# XMICRO-MEMORY_V1_0.net
KiCad netlist of a schematic drawn in EAGLE
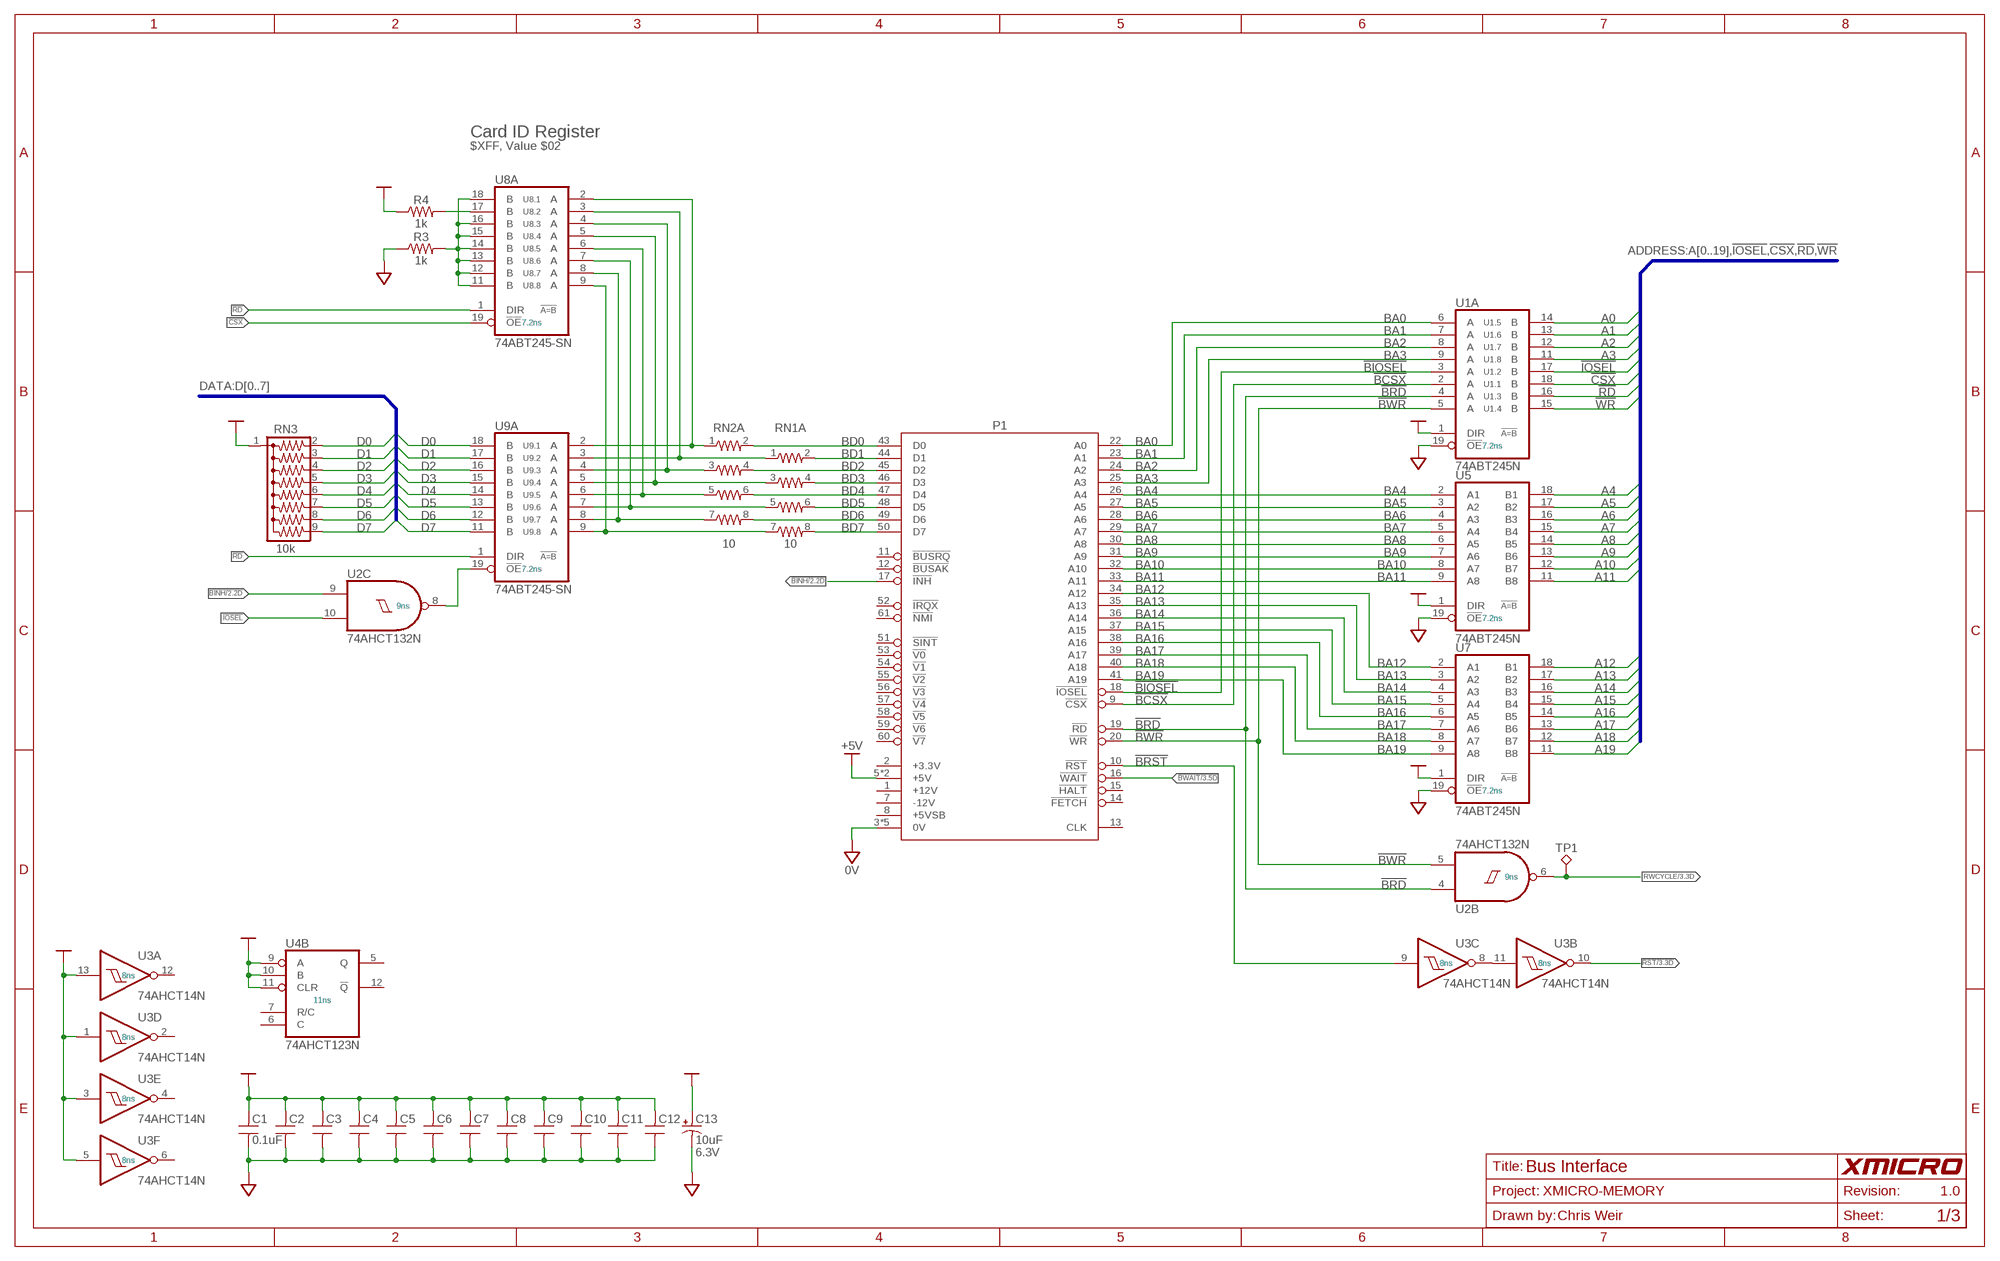
[diagram p0: schematic, sheet 1]
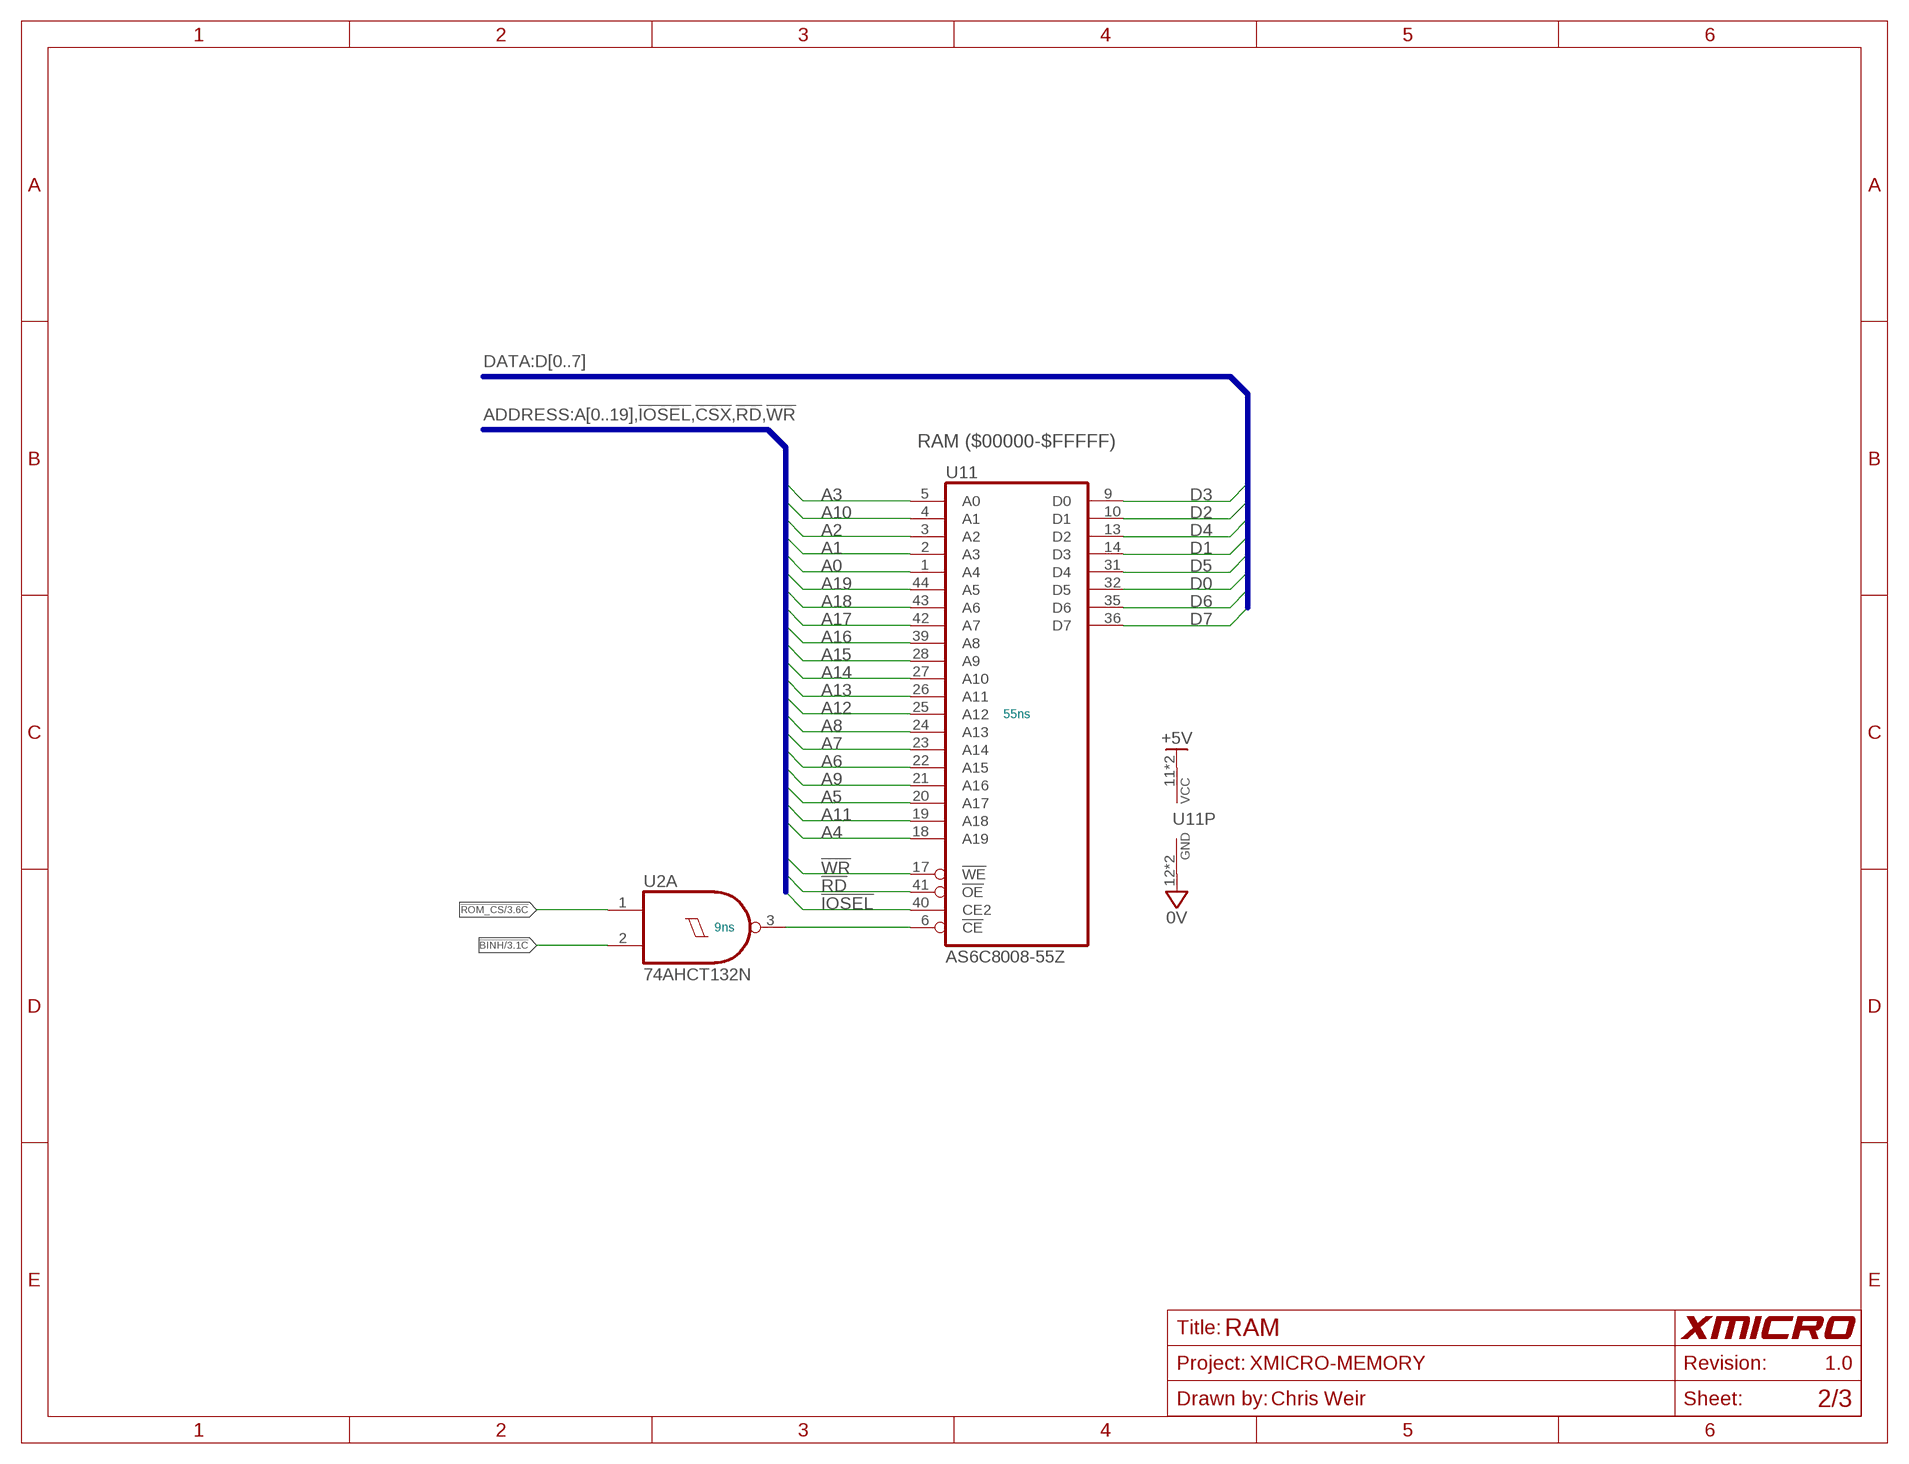
[diagram p1: schematic, sheet 2]
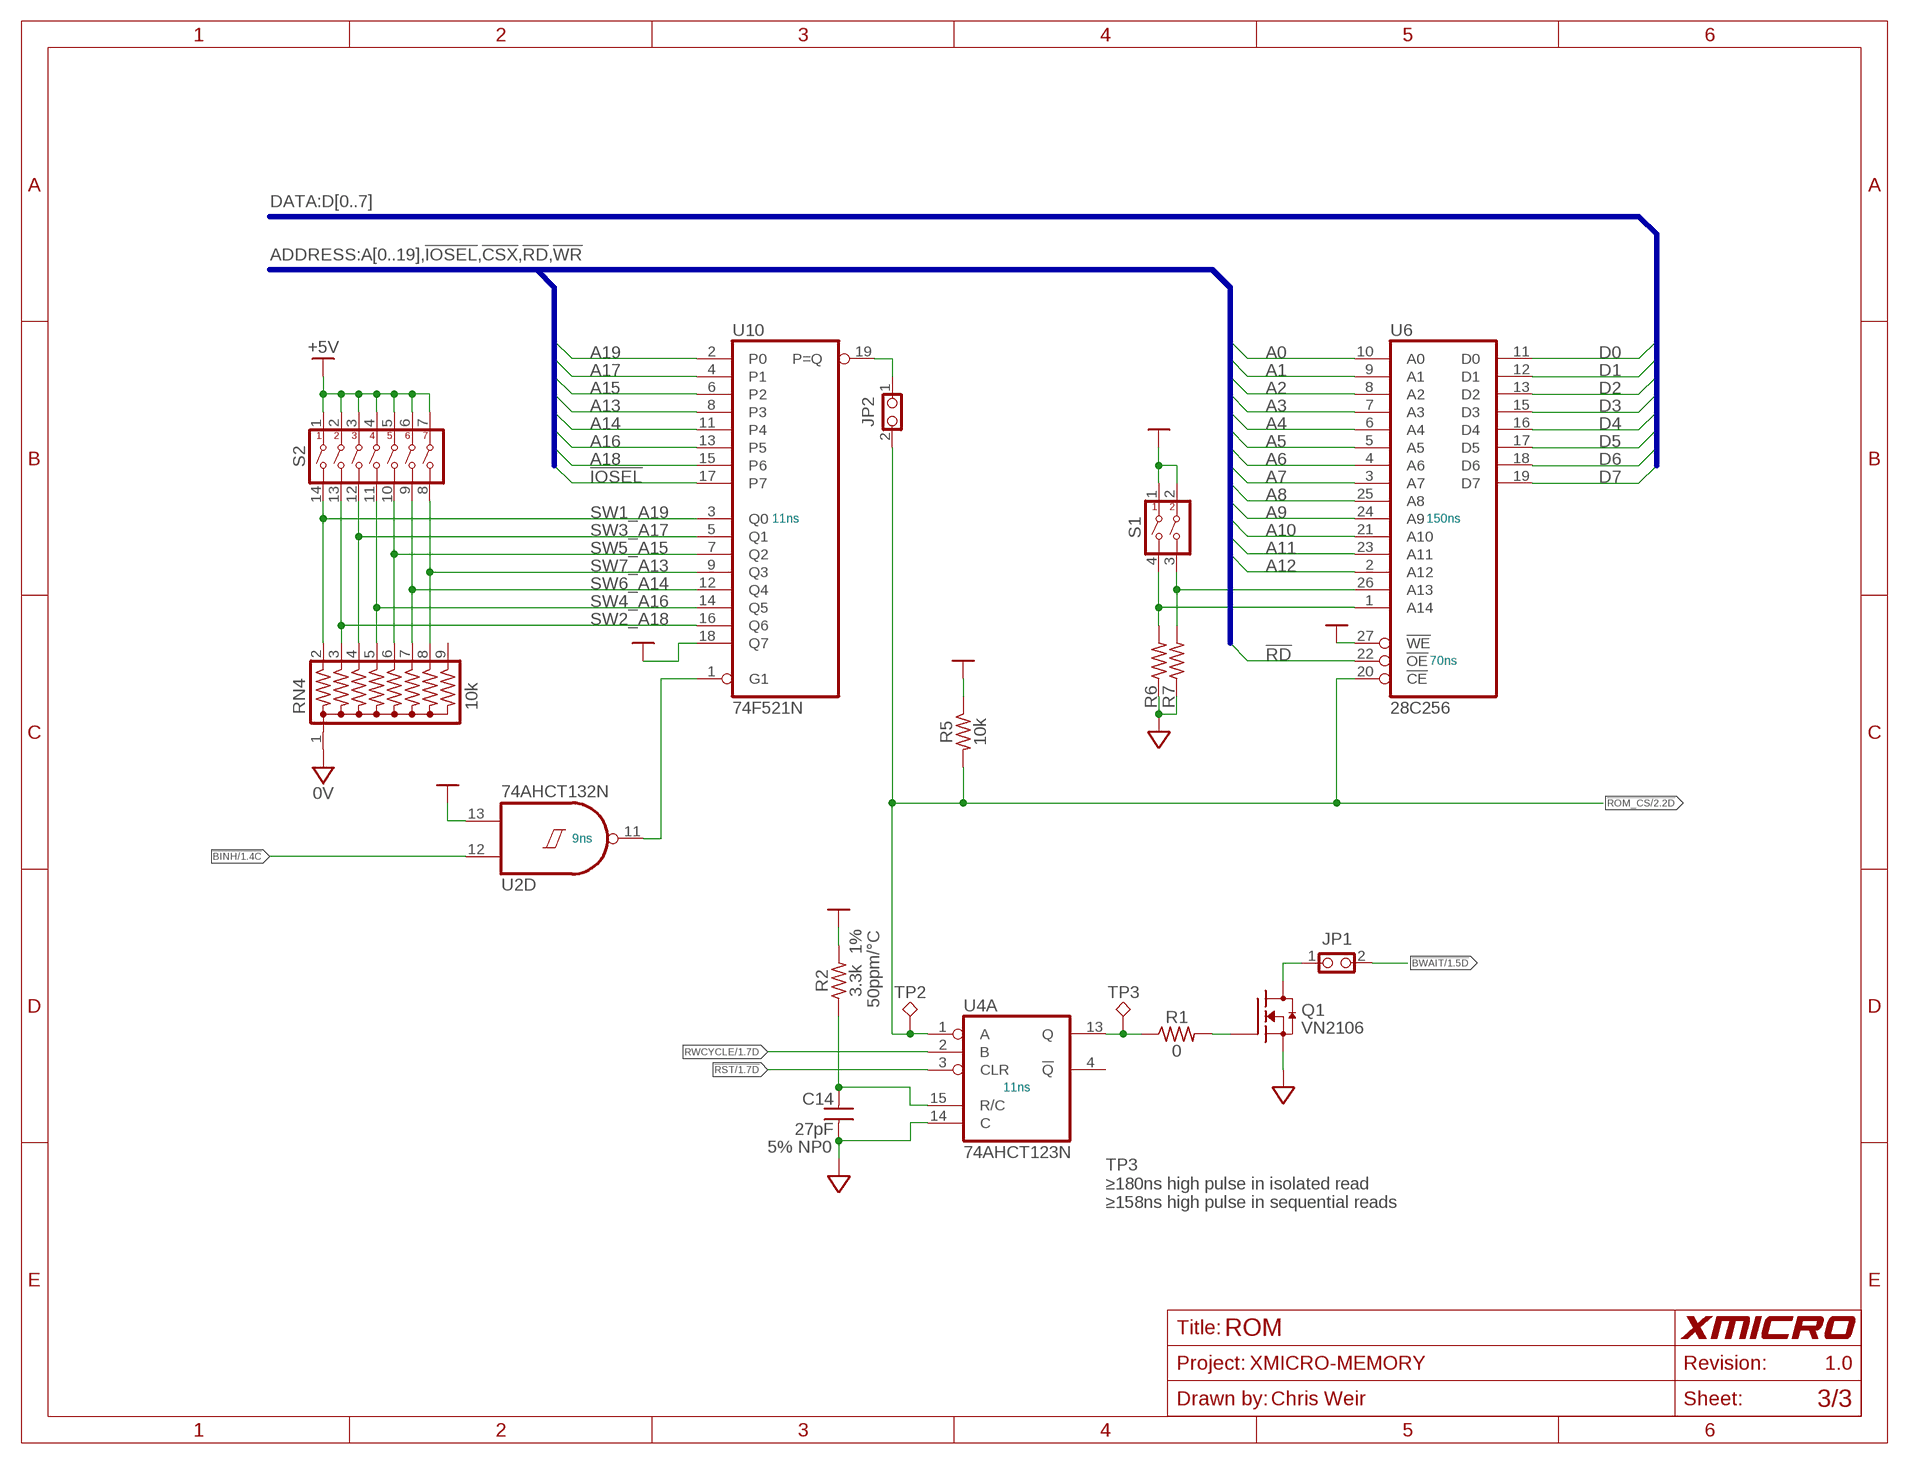
[diagram p2: schematic, sheet 3]

(export (version "E")
  (design (tool "Eeschema 10.0.6"))
  (components
    (comp (ref "C14")
      (value "27pF")
      (footprint "eagle-import:C025-024X044")
      (fields (field (name "TC") "NP0") (field (name "TOLERANCE") "5%"))
      (libsource (lib "eagle-import") (part "C-US025-024X044"))
    )
    (comp (ref "JP1")
      (value "1X2-THRU")
      (footprint "eagle-import:1X2")
      (libsource (lib "eagle-import") (part "1X2-THRU"))
    )
    (comp (ref "JP2")
      (value "1X2-THRU")
      (footprint "eagle-import:1X2")
      (libsource (lib "eagle-import") (part "1X2-THRU"))
    )
    (comp (ref "Q1")
      (value "VN2106")
      (footprint "eagle-import:TO92")
      (libsource (lib "eagle-import") (part "VN2106"))
    )
    (comp (ref "R1")
      (value "0")
      (footprint "eagle-import:0207_10")
      (libsource (lib "eagle-import") (part "R-US_0207/10"))
    )
    (comp (ref "R2")
      (value "3.3k")
      (footprint "eagle-import:0207_10")
      (fields (field (name "TC") "50ppm/°C") (field (name "TOLERANCE") "1%"))
      (libsource (lib "eagle-import") (part "R-US_0207/10"))
    )
    (comp (ref "R5")
      (value "10k")
      (footprint "eagle-import:0207_10")
      (libsource (lib "eagle-import") (part "R-US_0207/10"))
    )
    (comp (ref "R6")
      (value "10k")
      (footprint "eagle-import:0207_10")
      (libsource (lib "eagle-import") (part "R-US_0207/10"))
    )
    (comp (ref "R7")
      (value "10k")
      (footprint "eagle-import:0207_10")
      (libsource (lib "eagle-import") (part "R-US_0207/10"))
    )
    (comp (ref "RN4")
      (value "10k")
      (footprint "eagle-import:SIL9")
      (libsource (lib "eagle-import") (part "G08R"))
    )
    (comp (ref "S1")
      (value "SW-DIP02")
      (footprint "eagle-import:SW-DIP2")
      (libsource (lib "eagle-import") (part "SW-DIP02"))
    )
    (comp (ref "S2")
      (value "SW-DIP07")
      (footprint "eagle-import:SW-DIP7")
      (libsource (lib "eagle-import") (part "SW-DIP07"))
    )
    (comp (ref "TP2")
      (value "TP-040")
      (footprint "eagle-import:TP-040")
      (libsource (lib "eagle-import") (part "TP-040"))
    )
    (comp (ref "TP3")
      (value "TP-040")
      (footprint "eagle-import:TP-040")
      (libsource (lib "eagle-import") (part "TP-040"))
    )
    (comp (ref "U2")
      (value "74AHCT132N")
      (footprint "eagle-import:DIL14")
      (libsource (lib "eagle-import") (part "74132NAHCT"))
    )
    (comp (ref "U4")
      (value "74AHCT123N")
      (footprint "eagle-import:DIL16")
      (fields (field (name "TPD") "11ns"))
      (libsource (lib "eagle-import") (part "74123NAHCT"))
    )
    (comp (ref "U6")
      (value "28C256")
      (footprint "eagle-import:228-1277-00")
      (libsource (lib "eagle-import") (part "28256-P-ZC"))
    )
    (comp (ref "U10")
      (value "74F521N")
      (footprint "eagle-import:DIL20")
      (fields (field (name "TPD") "11ns"))
      (libsource (lib "eagle-import") (part "74521NF"))
    )
    (comp (ref "C1")
      (value "0.1uF")
      (footprint "eagle-import:C025-024X044")
      (libsource (lib "eagle-import") (part "C-US025-024X044"))
    )
    (comp (ref "C2")
      (value "0.1uF")
      (footprint "eagle-import:C025-024X044")
      (libsource (lib "eagle-import") (part "C-US025-024X044"))
    )
    (comp (ref "C3")
      (value "0.1uF")
      (footprint "eagle-import:C025-024X044")
      (libsource (lib "eagle-import") (part "C-US025-024X044"))
    )
    (comp (ref "C4")
      (value "0.1uF")
      (footprint "eagle-import:C025-024X044")
      (libsource (lib "eagle-import") (part "C-US025-024X044"))
    )
    (comp (ref "C5")
      (value "0.1uF")
      (footprint "eagle-import:C025-024X044")
      (libsource (lib "eagle-import") (part "C-US025-024X044"))
    )
    (comp (ref "C6")
      (value "0.1uF")
      (footprint "eagle-import:C025-024X044")
      (libsource (lib "eagle-import") (part "C-US025-024X044"))
    )
    (comp (ref "C7")
      (value "0.1uF")
      (footprint "eagle-import:C025-024X044")
      (libsource (lib "eagle-import") (part "C-US025-024X044"))
    )
    (comp (ref "C8")
      (value "0.1uF")
      (footprint "eagle-import:C025-024X044")
      (libsource (lib "eagle-import") (part "C-US025-024X044"))
    )
    (comp (ref "C9")
      (value "0.1uF")
      (footprint "eagle-import:C025-024X044")
      (libsource (lib "eagle-import") (part "C-US025-024X044"))
    )
    (comp (ref "C10")
      (value "0.1uF")
      (footprint "eagle-import:C025-024X044")
      (libsource (lib "eagle-import") (part "C-US025-024X044"))
    )
    (comp (ref "C11")
      (value "0.1uF")
      (footprint "eagle-import:C025-024X044")
      (libsource (lib "eagle-import") (part "C-US025-024X044"))
    )
    (comp (ref "C12")
      (value "0.1uF")
      (footprint "eagle-import:C025-024X044")
      (libsource (lib "eagle-import") (part "C-US025-024X044"))
    )
    (comp (ref "C13")
      (value "10uF")
      (footprint "eagle-import:E2,5-6")
      (fields (field (name "VOLTAGE") "6.3V"))
      (libsource (lib "eagle-import") (part "CPOL-USE2.5-6"))
    )
    (comp (ref "P1")
      (value "XMICRO-BUS-EDGE")
      (footprint "eagle-import:EDGE62M")
      (libsource (lib "eagle-import") (part "XMICRO-BUS-EDGE"))
    )
    (comp (ref "R3")
      (value "1k")
      (footprint "eagle-import:0207_10")
      (libsource (lib "eagle-import") (part "R-US_0207/10"))
    )
    (comp (ref "R4")
      (value "1k")
      (footprint "eagle-import:0207_10")
      (libsource (lib "eagle-import") (part "R-US_0207/10"))
    )
    (comp (ref "RN1")
      (value "10")
      (footprint "eagle-import:SIL8")
      (libsource (lib "eagle-import") (part "E4R"))
    )
    (comp (ref "RN2")
      (value "10")
      (footprint "eagle-import:SIL8")
      (libsource (lib "eagle-import") (part "E4R"))
    )
    (comp (ref "RN3")
      (value "10k")
      (footprint "eagle-import:SIL9")
      (libsource (lib "eagle-import") (part "G08R"))
    )
    (comp (ref "TP1")
      (value "TP-040")
      (footprint "eagle-import:TP-040")
      (libsource (lib "eagle-import") (part "TP-040"))
    )
    (comp (ref "U1")
      (value "74ABT245N")
      (footprint "eagle-import:DIL20")
      (libsource (lib "eagle-import") (part "74245-SNABT"))
    )
    (comp (ref "U3")
      (value "74AHCT14N")
      (footprint "eagle-import:DIL14")
      (fields (field (name "TPD") "8ns") (field (name "TPD_1") "8ns"))
      (libsource (lib "eagle-import") (part "7414NAHCT"))
    )
    (comp (ref "U5")
      (value "74ABT245N")
      (footprint "eagle-import:DIL20")
      (libsource (lib "eagle-import") (part "74245NABT"))
    )
    (comp (ref "U7")
      (value "74ABT245N")
      (footprint "eagle-import:DIL20")
      (libsource (lib "eagle-import") (part "74245NABT"))
    )
    (comp (ref "U8")
      (value "74ABT245-SN")
      (footprint "eagle-import:DIL20")
      (libsource (lib "eagle-import") (part "74245-SNABT"))
    )
    (comp (ref "U9")
      (value "74ABT245-SN")
      (footprint "eagle-import:DIL20")
      (libsource (lib "eagle-import") (part "74245-SNABT"))
    )
    (comp (ref "U11")
      (value "AS6C8008-55Z")
      (footprint "eagle-import:TSOP44-II")
      (libsource (lib "eagle-import") (part "AS6C8008-55Z"))
    )
  )
  (nets
    (net (code "28") (name "+5V") (class "Default")
      (node (ref "C1") (pin "1") (pinfunction "1_1") (pintype "passive"))
      (node (ref "C10") (pin "1") (pinfunction "1_1") (pintype "passive"))
      (node (ref "C11") (pin "1") (pinfunction "1_1") (pintype "passive"))
      (node (ref "C12") (pin "1") (pinfunction "1_1") (pintype "passive"))
      (node (ref "C13") (pin "+") (pinfunction "+_+") (pintype "passive"))
      (node (ref "C2") (pin "1") (pinfunction "1_1") (pintype "passive"))
      (node (ref "C3") (pin "1") (pinfunction "1_1") (pintype "passive"))
      (node (ref "C4") (pin "1") (pinfunction "1_1") (pintype "passive"))
      (node (ref "C5") (pin "1") (pinfunction "1_1") (pintype "passive"))
      (node (ref "C6") (pin "1") (pinfunction "1_1") (pintype "passive"))
      (node (ref "C7") (pin "1") (pinfunction "1_1") (pintype "passive"))
      (node (ref "C8") (pin "1") (pinfunction "1_1") (pintype "passive"))
      (node (ref "C9") (pin "1") (pinfunction "1_1") (pintype "passive"))
      (node (ref "P1") (pin "5") (pinfunction "+5V_5") (pintype "bidirectional"))
      (node (ref "P1") (pin "6") (pinfunction "+5V_6") (pintype "bidirectional"))
      (node (ref "R2") (pin "2") (pinfunction "2_2") (pintype "passive"))
      (node (ref "R4") (pin "1") (pinfunction "1_1") (pintype "passive"))
      (node (ref "R5") (pin "1") (pinfunction "1_1") (pintype "passive"))
      (node (ref "RN3") (pin "1") (pinfunction "1_1") (pintype "passive"))
      (node (ref "S1") (pin "1") (pinfunction "1_1") (pintype "passive"))
      (node (ref "S1") (pin "2") (pinfunction "2_2") (pintype "passive"))
      (node (ref "S2") (pin "1") (pinfunction "1_1") (pintype "passive"))
      (node (ref "S2") (pin "2") (pinfunction "2_2") (pintype "passive"))
      (node (ref "S2") (pin "3") (pinfunction "3_3") (pintype "passive"))
      (node (ref "S2") (pin "4") (pinfunction "4_4") (pintype "passive"))
      (node (ref "S2") (pin "5") (pinfunction "5_5") (pintype "passive"))
      (node (ref "S2") (pin "6") (pinfunction "6_6") (pintype "passive"))
      (node (ref "S2") (pin "7") (pinfunction "7_7") (pintype "passive"))
      (node (ref "U1") (pin "1") (pinfunction "DIR_1") (pintype "input"))
      (node (ref "U10") (pin "18") (pinfunction "Q7_18") (pintype "input"))
      (node (ref "U11") (pin "11") (pinfunction "+5V_11") (pintype "power_in"))
      (node (ref "U11") (pin "33") (pinfunction "+5V_33") (pintype "power_in"))
      (node (ref "U2") (pin "13") (pinfunction "I1_13") (pintype "input"))
      (node (ref "U3") (pin "1") (pinfunction "I_1") (pintype "input"))
      (node (ref "U3") (pin "13") (pinfunction "I_13") (pintype "input"))
      (node (ref "U3") (pin "3") (pinfunction "I_3") (pintype "input"))
      (node (ref "U3") (pin "5") (pinfunction "I_5") (pintype "input"))
      (node (ref "U4") (pin "10") (pinfunction "B_10") (pintype "input"))
      (node (ref "U4") (pin "11") (pinfunction "CLR_11") (pintype "input"))
      (node (ref "U4") (pin "9") (pinfunction "A_9") (pintype "input"))
      (node (ref "U5") (pin "1") (pinfunction "DIR_1") (pintype "input"))
      (node (ref "U6") (pin "27") (pinfunction "~{WE}_27") (pintype "input"))
      (node (ref "U7") (pin "1") (pinfunction "DIR_1") (pintype "input"))
    )
    (net (code "35") (name "0V") (class "Default")
      (node (ref "C1") (pin "2") (pinfunction "2_2") (pintype "passive"))
      (node (ref "C10") (pin "2") (pinfunction "2_2") (pintype "passive"))
      (node (ref "C11") (pin "2") (pinfunction "2_2") (pintype "passive"))
      (node (ref "C12") (pin "2") (pinfunction "2_2") (pintype "passive"))
      (node (ref "C13") (pin "-") (pinfunction "-_-") (pintype "passive"))
      (node (ref "C14") (pin "2") (pinfunction "2_2") (pintype "passive"))
      (node (ref "C2") (pin "2") (pinfunction "2_2") (pintype "passive"))
      (node (ref "C3") (pin "2") (pinfunction "2_2") (pintype "passive"))
      (node (ref "C4") (pin "2") (pinfunction "2_2") (pintype "passive"))
      (node (ref "C5") (pin "2") (pinfunction "2_2") (pintype "passive"))
      (node (ref "C6") (pin "2") (pinfunction "2_2") (pintype "passive"))
      (node (ref "C7") (pin "2") (pinfunction "2_2") (pintype "passive"))
      (node (ref "C8") (pin "2") (pinfunction "2_2") (pintype "passive"))
      (node (ref "C9") (pin "2") (pinfunction "2_2") (pintype "passive"))
      (node (ref "P1") (pin "21") (pinfunction "0V_21") (pintype "bidirectional"))
      (node (ref "P1") (pin "3") (pinfunction "0V_3") (pintype "bidirectional"))
      (node (ref "P1") (pin "4") (pinfunction "0V_4") (pintype "bidirectional"))
      (node (ref "P1") (pin "42") (pinfunction "0V_42") (pintype "bidirectional"))
      (node (ref "P1") (pin "62") (pinfunction "0V_62") (pintype "bidirectional"))
      (node (ref "Q1") (pin "1") (pinfunction "S_1") (pintype "passive"))
      (node (ref "R3") (pin "1") (pinfunction "1_1") (pintype "passive"))
      (node (ref "R6") (pin "1") (pinfunction "1_1") (pintype "passive"))
      (node (ref "R7") (pin "1") (pinfunction "1_1") (pintype "passive"))
      (node (ref "RN4") (pin "1") (pinfunction "1_1") (pintype "passive"))
      (node (ref "U1") (pin "19") (pinfunction "~{OE}_19") (pintype "input"))
      (node (ref "U11") (pin "12") (pinfunction "0V_12") (pintype "power_in"))
      (node (ref "U11") (pin "34") (pinfunction "0V_34") (pintype "power_in"))
      (node (ref "U4") (pin "14") (pinfunction "C_14") (pintype "input"))
      (node (ref "U5") (pin "19") (pinfunction "~{OE}_19") (pintype "input"))
      (node (ref "U7") (pin "19") (pinfunction "~{OE}_19") (pintype "input"))
    )
    (net (code "36") (name "A0") (class "Default")
      (node (ref "U1") (pin "14") (pinfunction "B_14") (pintype "bidirectional"))
      (node (ref "U11") (pin "1") (pinfunction "A4_1") (pintype "input"))
      (node (ref "U6") (pin "10") (pinfunction "A0_10") (pintype "input"))
    )
    (net (code "37") (name "A1") (class "Default")
      (node (ref "U1") (pin "13") (pinfunction "B_13") (pintype "bidirectional"))
      (node (ref "U11") (pin "2") (pinfunction "A3_2") (pintype "input"))
      (node (ref "U6") (pin "9") (pinfunction "A1_9") (pintype "input"))
    )
    (net (code "38") (name "A2") (class "Default")
      (node (ref "U1") (pin "12") (pinfunction "B_12") (pintype "bidirectional"))
      (node (ref "U11") (pin "3") (pinfunction "A2_3") (pintype "input"))
      (node (ref "U6") (pin "8") (pinfunction "A2_8") (pintype "input"))
    )
    (net (code "39") (name "A3") (class "Default")
      (node (ref "U1") (pin "11") (pinfunction "B_11") (pintype "bidirectional"))
      (node (ref "U11") (pin "5") (pinfunction "A0_5") (pintype "input"))
      (node (ref "U6") (pin "7") (pinfunction "A3_7") (pintype "input"))
    )
    (net (code "40") (name "A4") (class "Default")
      (node (ref "U11") (pin "18") (pinfunction "A19_18") (pintype "input"))
      (node (ref "U5") (pin "18") (pinfunction "B1_18") (pintype "bidirectional"))
      (node (ref "U6") (pin "6") (pinfunction "A4_6") (pintype "input"))
    )
    (net (code "41") (name "A5") (class "Default")
      (node (ref "U11") (pin "20") (pinfunction "A17_20") (pintype "input"))
      (node (ref "U5") (pin "17") (pinfunction "B2_17") (pintype "bidirectional"))
      (node (ref "U6") (pin "5") (pinfunction "A5_5") (pintype "input"))
    )
    (net (code "42") (name "A6") (class "Default")
      (node (ref "U11") (pin "22") (pinfunction "A15_22") (pintype "input"))
      (node (ref "U5") (pin "16") (pinfunction "B3_16") (pintype "bidirectional"))
      (node (ref "U6") (pin "4") (pinfunction "A6_4") (pintype "input"))
    )
    (net (code "43") (name "A7") (class "Default")
      (node (ref "U11") (pin "23") (pinfunction "A14_23") (pintype "input"))
      (node (ref "U5") (pin "15") (pinfunction "B4_15") (pintype "bidirectional"))
      (node (ref "U6") (pin "3") (pinfunction "A7_3") (pintype "input"))
    )
    (net (code "44") (name "A8") (class "Default")
      (node (ref "U11") (pin "24") (pinfunction "A13_24") (pintype "input"))
      (node (ref "U5") (pin "14") (pinfunction "B5_14") (pintype "bidirectional"))
      (node (ref "U6") (pin "25") (pinfunction "A8_25") (pintype "input"))
    )
    (net (code "45") (name "A9") (class "Default")
      (node (ref "U11") (pin "21") (pinfunction "A16_21") (pintype "input"))
      (node (ref "U5") (pin "13") (pinfunction "B6_13") (pintype "bidirectional"))
      (node (ref "U6") (pin "24") (pinfunction "A9_24") (pintype "input"))
    )
    (net (code "46") (name "A10") (class "Default")
      (node (ref "U11") (pin "4") (pinfunction "A1_4") (pintype "input"))
      (node (ref "U5") (pin "12") (pinfunction "B7_12") (pintype "bidirectional"))
      (node (ref "U6") (pin "21") (pinfunction "A10_21") (pintype "input"))
    )
    (net (code "47") (name "A11") (class "Default")
      (node (ref "U11") (pin "19") (pinfunction "A18_19") (pintype "input"))
      (node (ref "U5") (pin "11") (pinfunction "B8_11") (pintype "bidirectional"))
      (node (ref "U6") (pin "23") (pinfunction "A11_23") (pintype "input"))
    )
    (net (code "48") (name "A12") (class "Default")
      (node (ref "U11") (pin "25") (pinfunction "A12_25") (pintype "input"))
      (node (ref "U6") (pin "2") (pinfunction "A12_2") (pintype "input"))
      (node (ref "U7") (pin "18") (pinfunction "B1_18") (pintype "bidirectional"))
    )
    (net (code "49") (name "A13") (class "Default")
      (node (ref "U10") (pin "8") (pinfunction "P3_8") (pintype "input"))
      (node (ref "U11") (pin "26") (pinfunction "A11_26") (pintype "input"))
      (node (ref "U7") (pin "17") (pinfunction "B2_17") (pintype "bidirectional"))
    )
    (net (code "50") (name "A14") (class "Default")
      (node (ref "U10") (pin "11") (pinfunction "P4_11") (pintype "input"))
      (node (ref "U11") (pin "27") (pinfunction "A10_27") (pintype "input"))
      (node (ref "U7") (pin "16") (pinfunction "B3_16") (pintype "bidirectional"))
    )
    (net (code "51") (name "A15") (class "Default")
      (node (ref "U10") (pin "6") (pinfunction "P2_6") (pintype "input"))
      (node (ref "U11") (pin "28") (pinfunction "A9_28") (pintype "input"))
      (node (ref "U7") (pin "15") (pinfunction "B4_15") (pintype "bidirectional"))
    )
    (net (code "52") (name "A16") (class "Default")
      (node (ref "U10") (pin "13") (pinfunction "P5_13") (pintype "input"))
      (node (ref "U11") (pin "39") (pinfunction "A8_39") (pintype "input"))
      (node (ref "U7") (pin "14") (pinfunction "B5_14") (pintype "bidirectional"))
    )
    (net (code "53") (name "A17") (class "Default")
      (node (ref "U10") (pin "4") (pinfunction "P1_4") (pintype "input"))
      (node (ref "U11") (pin "42") (pinfunction "A7_42") (pintype "input"))
      (node (ref "U7") (pin "13") (pinfunction "B6_13") (pintype "bidirectional"))
    )
    (net (code "54") (name "A18") (class "Default")
      (node (ref "U10") (pin "15") (pinfunction "P6_15") (pintype "input"))
      (node (ref "U11") (pin "43") (pinfunction "A6_43") (pintype "input"))
      (node (ref "U7") (pin "12") (pinfunction "B7_12") (pintype "bidirectional"))
    )
    (net (code "55") (name "A19") (class "Default")
      (node (ref "U10") (pin "2") (pinfunction "P0_2") (pintype "input"))
      (node (ref "U11") (pin "44") (pinfunction "A5_44") (pintype "input"))
      (node (ref "U7") (pin "11") (pinfunction "B8_11") (pintype "bidirectional"))
    )
    (net (code "56") (name "BA0") (class "Default")
      (node (ref "P1") (pin "22") (pinfunction "A0_22") (pintype "bidirectional"))
      (node (ref "U1") (pin "6") (pinfunction "A_6") (pintype "bidirectional"))
    )
    (net (code "57") (name "BA1") (class "Default")
      (node (ref "P1") (pin "23") (pinfunction "A1_23") (pintype "bidirectional"))
      (node (ref "U1") (pin "7") (pinfunction "A_7") (pintype "bidirectional"))
    )
    (net (code "58") (name "BA2") (class "Default")
      (node (ref "P1") (pin "24") (pinfunction "A2_24") (pintype "bidirectional"))
      (node (ref "U1") (pin "8") (pinfunction "A_8") (pintype "bidirectional"))
    )
    (net (code "59") (name "BA3") (class "Default")
      (node (ref "P1") (pin "25") (pinfunction "A3_25") (pintype "bidirectional"))
      (node (ref "U1") (pin "9") (pinfunction "A_9") (pintype "bidirectional"))
    )
    (net (code "60") (name "BA4") (class "Default")
      (node (ref "P1") (pin "26") (pinfunction "A4_26") (pintype "bidirectional"))
      (node (ref "U5") (pin "2") (pinfunction "A1_2") (pintype "bidirectional"))
    )
    (net (code "61") (name "BA5") (class "Default")
      (node (ref "P1") (pin "27") (pinfunction "A5_27") (pintype "bidirectional"))
      (node (ref "U5") (pin "3") (pinfunction "A2_3") (pintype "bidirectional"))
    )
    (net (code "62") (name "BA6") (class "Default")
      (node (ref "P1") (pin "28") (pinfunction "A6_28") (pintype "bidirectional"))
      (node (ref "U5") (pin "4") (pinfunction "A3_4") (pintype "bidirectional"))
    )
    (net (code "63") (name "BA7") (class "Default")
      (node (ref "P1") (pin "29") (pinfunction "A7_29") (pintype "bidirectional"))
      (node (ref "U5") (pin "5") (pinfunction "A4_5") (pintype "bidirectional"))
    )
    (net (code "64") (name "BA8") (class "Default")
      (node (ref "P1") (pin "30") (pinfunction "A8_30") (pintype "bidirectional"))
      (node (ref "U5") (pin "6") (pinfunction "A5_6") (pintype "bidirectional"))
    )
    (net (code "65") (name "BA9") (class "Default")
      (node (ref "P1") (pin "31") (pinfunction "A9_31") (pintype "bidirectional"))
      (node (ref "U5") (pin "7") (pinfunction "A6_7") (pintype "bidirectional"))
    )
    (net (code "66") (name "BA10") (class "Default")
      (node (ref "P1") (pin "32") (pinfunction "A10_32") (pintype "bidirectional"))
      (node (ref "U5") (pin "8") (pinfunction "A7_8") (pintype "bidirectional"))
    )
    (net (code "67") (name "BA11") (class "Default")
      (node (ref "P1") (pin "33") (pinfunction "A11_33") (pintype "bidirectional"))
      (node (ref "U5") (pin "9") (pinfunction "A8_9") (pintype "bidirectional"))
    )
    (net (code "68") (name "BA12") (class "Default")
      (node (ref "P1") (pin "34") (pinfunction "A12_34") (pintype "bidirectional"))
      (node (ref "U7") (pin "2") (pinfunction "A1_2") (pintype "bidirectional"))
    )
    (net (code "69") (name "BA13") (class "Default")
      (node (ref "P1") (pin "35") (pinfunction "A13_35") (pintype "bidirectional"))
      (node (ref "U7") (pin "3") (pinfunction "A2_3") (pintype "bidirectional"))
    )
    (net (code "70") (name "BA14") (class "Default")
      (node (ref "P1") (pin "36") (pinfunction "A14_36") (pintype "bidirectional"))
      (node (ref "U7") (pin "4") (pinfunction "A3_4") (pintype "bidirectional"))
    )
    (net (code "71") (name "BA15") (class "Default")
      (node (ref "P1") (pin "37") (pinfunction "A15_37") (pintype "bidirectional"))
      (node (ref "U7") (pin "5") (pinfunction "A4_5") (pintype "bidirectional"))
    )
    (net (code "72") (name "BA16") (class "Default")
      (node (ref "P1") (pin "38") (pinfunction "A16_38") (pintype "bidirectional"))
      (node (ref "U7") (pin "6") (pinfunction "A5_6") (pintype "bidirectional"))
    )
    (net (code "73") (name "BA17") (class "Default")
      (node (ref "P1") (pin "39") (pinfunction "A17_39") (pintype "bidirectional"))
      (node (ref "U7") (pin "7") (pinfunction "A6_7") (pintype "bidirectional"))
    )
    (net (code "74") (name "BA18") (class "Default")
      (node (ref "P1") (pin "40") (pinfunction "A18_40") (pintype "bidirectional"))
      (node (ref "U7") (pin "8") (pinfunction "A7_8") (pintype "bidirectional"))
    )
    (net (code "75") (name "BA19") (class "Default")
      (node (ref "P1") (pin "41") (pinfunction "A19_41") (pintype "bidirectional"))
      (node (ref "U7") (pin "9") (pinfunction "A8_9") (pintype "bidirectional"))
    )
    (net (code "76") (name "BD0") (class "Default")
      (node (ref "P1") (pin "43") (pinfunction "D0_43") (pintype "bidirectional"))
      (node (ref "RN2") (pin "2") (pinfunction "2_2") (pintype "passive"))
    )
    (net (code "77") (name "BD1") (class "Default")
      (node (ref "P1") (pin "44") (pinfunction "D1_44") (pintype "bidirectional"))
      (node (ref "RN1") (pin "2") (pinfunction "2_2") (pintype "passive"))
    )
    (net (code "78") (name "BD2") (class "Default")
      (node (ref "P1") (pin "45") (pinfunction "D2_45") (pintype "bidirectional"))
      (node (ref "RN2") (pin "4") (pinfunction "2_4") (pintype "passive"))
    )
    (net (code "79") (name "BD3") (class "Default")
      (node (ref "P1") (pin "46") (pinfunction "D3_46") (pintype "bidirectional"))
      (node (ref "RN1") (pin "4") (pinfunction "2_4") (pintype "passive"))
    )
    (net (code "80") (name "BD4") (class "Default")
      (node (ref "P1") (pin "47") (pinfunction "D4_47") (pintype "bidirectional"))
      (node (ref "RN2") (pin "6") (pinfunction "2_6") (pintype "passive"))
    )
    (net (code "81") (name "BD5") (class "Default")
      (node (ref "P1") (pin "48") (pinfunction "D5_48") (pintype "bidirectional"))
      (node (ref "RN1") (pin "6") (pinfunction "2_6") (pintype "passive"))
    )
    (net (code "82") (name "BD6") (class "Default")
      (node (ref "P1") (pin "49") (pinfunction "D6_49") (pintype "bidirectional"))
      (node (ref "RN2") (pin "8") (pinfunction "2_8") (pintype "passive"))
    )
    (net (code "83") (name "BD7") (class "Default")
      (node (ref "P1") (pin "50") (pinfunction "D7_50") (pintype "bidirectional"))
      (node (ref "RN1") (pin "8") (pinfunction "2_8") (pintype "passive"))
    )
    (net (code "84") (name "D0") (class "Default")
      (node (ref "RN3") (pin "2") (pinfunction "2_2") (pintype "passive"))
      (node (ref "U11") (pin "32") (pinfunction "D5_32") (pintype "tri_state"))
      (node (ref "U6") (pin "11") (pinfunction "D0_11") (pintype "tri_state"))
      (node (ref "U9") (pin "18") (pinfunction "B_18") (pintype "bidirectional"))
    )
    (net (code "85") (name "D1") (class "Default")
      (node (ref "RN3") (pin "3") (pinfunction "3_3") (pintype "passive"))
      (node (ref "U11") (pin "14") (pinfunction "D3_14") (pintype "tri_state"))
      (node (ref "U6") (pin "12") (pinfunction "D1_12") (pintype "tri_state"))
      (node (ref "U9") (pin "17") (pinfunction "B_17") (pintype "bidirectional"))
    )
    (net (code "86") (name "D2") (class "Default")
      (node (ref "RN3") (pin "4") (pinfunction "4_4") (pintype "passive"))
      (node (ref "U11") (pin "10") (pinfunction "D1_10") (pintype "tri_state"))
      (node (ref "U6") (pin "13") (pinfunction "D2_13") (pintype "tri_state"))
      (node (ref "U9") (pin "16") (pinfunction "B_16") (pintype "bidirectional"))
    )
    (net (code "87") (name "D3") (class "Default")
      (node (ref "RN3") (pin "5") (pinfunction "5_5") (pintype "passive"))
      (node (ref "U11") (pin "9") (pinfunction "D0_9") (pintype "tri_state"))
      (node (ref "U6") (pin "15") (pinfunction "D3_15") (pintype "tri_state"))
      (node (ref "U9") (pin "15") (pinfunction "B_15") (pintype "bidirectional"))
    )
    (net (code "88") (name "D4") (class "Default")
      (node (ref "RN3") (pin "6") (pinfunction "6_6") (pintype "passive"))
      (node (ref "U11") (pin "13") (pinfunction "D2_13") (pintype "tri_state"))
      (node (ref "U6") (pin "16") (pinfunction "D4_16") (pintype "tri_state"))
      (node (ref "U9") (pin "14") (pinfunction "B_14") (pintype "bidirectional"))
    )
    (net (code "89") (name "D5") (class "Default")
      (node (ref "RN3") (pin "7") (pinfunction "7_7") (pintype "passive"))
      (node (ref "U11") (pin "31") (pinfunction "D4_31") (pintype "tri_state"))
      (node (ref "U6") (pin "17") (pinfunction "D5_17") (pintype "tri_state"))
      (node (ref "U9") (pin "13") (pinfunction "B_13") (pintype "bidirectional"))
    )
    (net (code "90") (name "D6") (class "Default")
      (node (ref "RN3") (pin "8") (pinfunction "8_8") (pintype "passive"))
      (node (ref "U11") (pin "35") (pinfunction "D6_35") (pintype "tri_state"))
      (node (ref "U6") (pin "18") (pinfunction "D6_18") (pintype "tri_state"))
      (node (ref "U9") (pin "12") (pinfunction "B_12") (pintype "bidirectional"))
    )
    (net (code "91") (name "D7") (class "Default")
      (node (ref "RN3") (pin "9") (pinfunction "9_9") (pintype "passive"))
      (node (ref "U11") (pin "36") (pinfunction "D7_36") (pintype "tri_state"))
      (node (ref "U6") (pin "19") (pinfunction "D7_19") (pintype "tri_state"))
      (node (ref "U9") (pin "11") (pinfunction "B_11") (pintype "bidirectional"))
    )
    (net (code "92") (name "Net-(Q1-D)") (class "Default")
      (node (ref "JP1") (pin "1") (pinfunction "1_1") (pintype "passive"))
      (node (ref "Q1") (pin "3") (pinfunction "D_3") (pintype "passive"))
    )
    (net (code "93") (name "Net-(Q1-G)") (class "Default")
      (node (ref "Q1") (pin "2") (pinfunction "G_2") (pintype "passive"))
      (node (ref "R1") (pin "2") (pinfunction "2_2") (pintype "passive"))
    )
    (net (code "94") (name "Net-(RN1B-1)") (class "Default")
      (node (ref "RN1") (pin "3") (pinfunction "1_3") (pintype "passive"))
      (node (ref "U8") (pin "5") (pinfunction "A_5") (pintype "bidirectional"))
      (node (ref "U9") (pin "5") (pinfunction "A_5") (pintype "bidirectional"))
    )
    (net (code "95") (name "Net-(RN1C-1)") (class "Default")
      (node (ref "RN1") (pin "5") (pinfunction "1_5") (pintype "passive"))
      (node (ref "U8") (pin "7") (pinfunction "A_7") (pintype "bidirectional"))
      (node (ref "U9") (pin "7") (pinfunction "A_7") (pintype "bidirectional"))
    )
    (net (code "96") (name "Net-(RN1D-1)") (class "Default")
      (node (ref "RN1") (pin "7") (pinfunction "1_7") (pintype "passive"))
      (node (ref "U8") (pin "9") (pinfunction "A_9") (pintype "bidirectional"))
      (node (ref "U9") (pin "9") (pinfunction "A_9") (pintype "bidirectional"))
    )
    (net (code "97") (name "Net-(RN2B-1)") (class "Default")
      (node (ref "RN2") (pin "3") (pinfunction "1_3") (pintype "passive"))
      (node (ref "U8") (pin "4") (pinfunction "A_4") (pintype "bidirectional"))
      (node (ref "U9") (pin "4") (pinfunction "A_4") (pintype "bidirectional"))
    )
    (net (code "98") (name "Net-(RN2C-1)") (class "Default")
      (node (ref "RN2") (pin "5") (pinfunction "1_5") (pintype "passive"))
      (node (ref "U8") (pin "6") (pinfunction "A_6") (pintype "bidirectional"))
      (node (ref "U9") (pin "6") (pinfunction "A_6") (pintype "bidirectional"))
    )
    (net (code "99") (name "Net-(RN2D-1)") (class "Default")
      (node (ref "RN2") (pin "7") (pinfunction "1_7") (pintype "passive"))
      (node (ref "U8") (pin "8") (pinfunction "A_8") (pintype "bidirectional"))
      (node (ref "U9") (pin "8") (pinfunction "A_8") (pintype "bidirectional"))
    )
    (net (code "100") (name "Net-(U2C-O)") (class "Default")
      (node (ref "U2") (pin "8") (pinfunction "O_8") (pintype "output"))
      (node (ref "U9") (pin "19") (pinfunction "~{OE}_19") (pintype "input"))
    )
    (net (code "101") (name "Net-(U3B-I)") (class "Default")
      (node (ref "U3") (pin "11") (pinfunction "I_11") (pintype "input"))
      (node (ref "U3") (pin "8") (pinfunction "O_8") (pintype "output"))
    )
    (net (code "102") (name "Net-(U4A-Q)") (class "Default")
      (node (ref "R1") (pin "1") (pinfunction "1_1") (pintype "passive"))
      (node (ref "TP3") (pin "1") (pinfunction "1_1") (pintype "passive"))
      (node (ref "U4") (pin "13") (pinfunction "Q_13") (pintype "output"))
    )
    (net (code "103") (name "Net-(U4A-R{slash}C)") (class "Default")
      (node (ref "C14") (pin "1") (pinfunction "1_1") (pintype "passive"))
      (node (ref "R2") (pin "1") (pinfunction "1_1") (pintype "passive"))
      (node (ref "U4") (pin "15") (pinfunction "R/C_15") (pintype "input"))
    )
    (net (code "104") (name "Net-(U6A-A13)") (class "Default")
      (node (ref "R7") (pin "2") (pinfunction "2_2") (pintype "passive"))
      (node (ref "S1") (pin "3") (pinfunction "3_3") (pintype "passive"))
      (node (ref "U6") (pin "26") (pinfunction "A13_26") (pintype "input"))
    )
    (net (code "105") (name "Net-(U6A-A14)") (class "Default")
      (node (ref "R6") (pin "2") (pinfunction "2_2") (pintype "passive"))
      (node (ref "S1") (pin "4") (pinfunction "4_4") (pintype "passive"))
      (node (ref "U6") (pin "1") (pinfunction "A14_1") (pintype "input"))
    )
    (net (code "106") (name "Net-(U8A-A)") (class "Default")
      (node (ref "RN2") (pin "1") (pinfunction "1_1") (pintype "passive"))
      (node (ref "U8") (pin "2") (pinfunction "A_2") (pintype "bidirectional"))
      (node (ref "U9") (pin "2") (pinfunction "A_2") (pintype "bidirectional"))
    )
    (net (code "107") (name "Net-(U8A-B)") (class "Default")
      (node (ref "R3") (pin "2") (pinfunction "2_2") (pintype "passive"))
      (node (ref "U8") (pin "11") (pinfunction "B_11") (pintype "bidirectional"))
      (node (ref "U8") (pin "12") (pinfunction "B_12") (pintype "bidirectional"))
      (node (ref "U8") (pin "13") (pinfunction "B_13") (pintype "bidirectional"))
      (node (ref "U8") (pin "14") (pinfunction "B_14") (pintype "bidirectional"))
      (node (ref "U8") (pin "15") (pinfunction "B_15") (pintype "bidirectional"))
      (node (ref "U8") (pin "16") (pinfunction "B_16") (pintype "bidirectional"))
      (node (ref "U8") (pin "18") (pinfunction "B_18") (pintype "bidirectional"))
    )
    (net (code "108") (name "Net-(U8B-A)") (class "Default")
      (node (ref "RN1") (pin "1") (pinfunction "1_1") (pintype "passive"))
      (node (ref "U8") (pin "3") (pinfunction "A_3") (pintype "bidirectional"))
      (node (ref "U9") (pin "3") (pinfunction "A_3") (pintype "bidirectional"))
    )
    (net (code "109") (name "Net-(U8B-B)") (class "Default")
      (node (ref "R4") (pin "2") (pinfunction "2_2") (pintype "passive"))
      (node (ref "U8") (pin "17") (pinfunction "B_17") (pintype "bidirectional"))
    )
    (net (code "110") (name "Net-(U10A-G1)") (class "Default")
      (node (ref "U10") (pin "1") (pinfunction "G1_1") (pintype "input"))
      (node (ref "U2") (pin "11") (pinfunction "O_11") (pintype "output"))
    )
    (net (code "111") (name "Net-(U10A-P=Q)") (class "Default")
      (node (ref "JP2") (pin "1") (pinfunction "1_1") (pintype "passive"))
      (node (ref "U10") (pin "19") (pinfunction "P=Q_19") (pintype "output"))
    )
    (net (code "112") (name "Net-(U11A-~{CE})") (class "Default")
      (node (ref "U11") (pin "6") (pinfunction "~{CE}_6") (pintype "input"))
      (node (ref "U2") (pin "3") (pinfunction "O_3") (pintype "output"))
    )
    (net (code "113") (name "RWCYCLE") (class "Default")
      (node (ref "TP1") (pin "1") (pinfunction "1_1") (pintype "passive"))
      (node (ref "U2") (pin "6") (pinfunction "O_6") (pintype "output"))
      (node (ref "U4") (pin "2") (pinfunction "B_2") (pintype "input"))
    )
    (net (code "114") (name "SW1_A19") (class "Default")
      (node (ref "RN4") (pin "2") (pinfunction "2_2") (pintype "passive"))
      (node (ref "S2") (pin "14") (pinfunction "14_14") (pintype "passive"))
      (node (ref "U10") (pin "3") (pinfunction "Q0_3") (pintype "input"))
    )
    (net (code "115") (name "SW2_A18") (class "Default")
      (node (ref "RN4") (pin "3") (pinfunction "3_3") (pintype "passive"))
      (node (ref "S2") (pin "13") (pinfunction "13_13") (pintype "passive"))
      (node (ref "U10") (pin "16") (pinfunction "Q6_16") (pintype "input"))
    )
    (net (code "116") (name "SW3_A17") (class "Default")
      (node (ref "RN4") (pin "4") (pinfunction "4_4") (pintype "passive"))
      (node (ref "S2") (pin "12") (pinfunction "12_12") (pintype "passive"))
      (node (ref "U10") (pin "5") (pinfunction "Q1_5") (pintype "input"))
    )
    (net (code "117") (name "SW4_A16") (class "Default")
      (node (ref "RN4") (pin "5") (pinfunction "5_5") (pintype "passive"))
      (node (ref "S2") (pin "11") (pinfunction "11_11") (pintype "passive"))
      (node (ref "U10") (pin "14") (pinfunction "Q5_14") (pintype "input"))
    )
    (net (code "118") (name "SW5_A15") (class "Default")
      (node (ref "RN4") (pin "6") (pinfunction "6_6") (pintype "passive"))
      (node (ref "S2") (pin "10") (pinfunction "10_10") (pintype "passive"))
      (node (ref "U10") (pin "7") (pinfunction "Q2_7") (pintype "input"))
    )
    (net (code "119") (name "SW6_A14") (class "Default")
      (node (ref "RN4") (pin "7") (pinfunction "7_7") (pintype "passive"))
      (node (ref "S2") (pin "9") (pinfunction "9_9") (pintype "passive"))
      (node (ref "U10") (pin "12") (pinfunction "Q4_12") (pintype "input"))
    )
    (net (code "120") (name "SW7_A13") (class "Default")
      (node (ref "RN4") (pin "8") (pinfunction "8_8") (pintype "passive"))
      (node (ref "S2") (pin "8") (pinfunction "8_8") (pintype "passive"))
      (node (ref "U10") (pin "9") (pinfunction "Q3_9") (pintype "input"))
    )
    (net (code "121") (name "unconnected-(P1-+3.3V-Pad2)") (class "Default")
      (node (ref "P1") (pin "2") (pinfunction "+3.3V_2") (pintype "bidirectional"))
    )
    (net (code "122") (name "unconnected-(P1-+5VSB-Pad8)") (class "Default")
      (node (ref "P1") (pin "8") (pinfunction "+5VSB_8") (pintype "bidirectional"))
    )
    (net (code "123") (name "unconnected-(P1-+12V-Pad1)") (class "Default")
      (node (ref "P1") (pin "1") (pinfunction "+12V_1") (pintype "bidirectional"))
    )
    (net (code "124") (name "unconnected-(P1--12V-Pad7)") (class "Default")
      (node (ref "P1") (pin "7") (pinfunction "-12V_7") (pintype "bidirectional"))
    )
    (net (code "125") (name "unconnected-(P1-CLK-Pad13)") (class "Default")
      (node (ref "P1") (pin "13") (pinfunction "CLK_13") (pintype "bidirectional"))
    )
    (net (code "126") (name "unconnected-(P1-~{BUSAK}-Pad12)") (class "Default")
      (node (ref "P1") (pin "12") (pinfunction "~{BUSAK}_12") (pintype "bidirectional"))
    )
    (net (code "127") (name "unconnected-(P1-~{BUSRQ}-Pad11)") (class "Default")
      (node (ref "P1") (pin "11") (pinfunction "~{BUSRQ}_11") (pintype "bidirectional"))
    )
    (net (code "128") (name "unconnected-(P1-~{FETCH}-Pad14)") (class "Default")
      (node (ref "P1") (pin "14") (pinfunction "~{FETCH}_14") (pintype "bidirectional"))
    )
    (net (code "129") (name "unconnected-(P1-~{HALT}-Pad15)") (class "Default")
      (node (ref "P1") (pin "15") (pinfunction "~{HALT}_15") (pintype "bidirectional"))
    )
    (net (code "130") (name "unconnected-(P1-~{IRQX}-Pad52)") (class "Default")
      (node (ref "P1") (pin "52") (pinfunction "~{IRQX}_52") (pintype "bidirectional"))
    )
    (net (code "131") (name "unconnected-(P1-~{NMI}-Pad61)") (class "Default")
      (node (ref "P1") (pin "61") (pinfunction "~{NMI}_61") (pintype "bidirectional"))
    )
    (net (code "132") (name "unconnected-(P1-~{SINT}-Pad51)") (class "Default")
      (node (ref "P1") (pin "51") (pinfunction "~{SINT}_51") (pintype "bidirectional"))
    )
    (net (code "133") (name "unconnected-(P1-~{V0}-Pad53)") (class "Default")
      (node (ref "P1") (pin "53") (pinfunction "~{V0}_53") (pintype "bidirectional"))
    )
    (net (code "134") (name "unconnected-(P1-~{V1}-Pad54)") (class "Default")
      (node (ref "P1") (pin "54") (pinfunction "~{V1}_54") (pintype "bidirectional"))
    )
    (net (code "135") (name "unconnected-(P1-~{V2}-Pad55)") (class "Default")
      (node (ref "P1") (pin "55") (pinfunction "~{V2}_55") (pintype "bidirectional"))
    )
    (net (code "136") (name "unconnected-(P1-~{V3}-Pad56)") (class "Default")
      (node (ref "P1") (pin "56") (pinfunction "~{V3}_56") (pintype "bidirectional"))
    )
    (net (code "137") (name "unconnected-(P1-~{V4}-Pad57)") (class "Default")
      (node (ref "P1") (pin "57") (pinfunction "~{V4}_57") (pintype "bidirectional"))
    )
    (net (code "138") (name "unconnected-(P1-~{V5}-Pad58)") (class "Default")
      (node (ref "P1") (pin "58") (pinfunction "~{V5}_58") (pintype "bidirectional"))
    )
    (net (code "139") (name "unconnected-(P1-~{V6}-Pad59)") (class "Default")
      (node (ref "P1") (pin "59") (pinfunction "~{V6}_59") (pintype "bidirectional"))
    )
    (net (code "140") (name "unconnected-(P1-~{V7}-Pad60)") (class "Default")
      (node (ref "P1") (pin "60") (pinfunction "~{V7}_60") (pintype "bidirectional"))
    )
    (net (code "141") (name "unconnected-(RN4-Pad9)") (class "Default")
      (node (ref "RN4") (pin "9") (pinfunction "9_9") (pintype "passive"))
    )
    (net (code "142") (name "unconnected-(U3A-O-Pad12)") (class "Default")
      (node (ref "U3") (pin "12") (pinfunction "O_12") (pintype "output"))
    )
    (net (code "143") (name "unconnected-(U3D-O-Pad2)") (class "Default")
      (node (ref "U3") (pin "2") (pinfunction "O_2") (pintype "output"))
    )
    (net (code "144") (name "unconnected-(U3E-O-Pad4)") (class "Default")
      (node (ref "U3") (pin "4") (pinfunction "O_4") (pintype "output"))
    )
    (net (code "145") (name "unconnected-(U3F-O-Pad6)") (class "Default")
      (node (ref "U3") (pin "6") (pinfunction "O_6") (pintype "output"))
    )
    (net (code "146") (name "unconnected-(U4A-~{Q}-Pad4)") (class "Default")
      (node (ref "U4") (pin "4") (pinfunction "~{Q}_4") (pintype "output"))
    )
    (net (code "147") (name "unconnected-(U4B-C-Pad6)") (class "Default")
      (node (ref "U4") (pin "6") (pinfunction "C_6") (pintype "input"))
    )
    (net (code "148") (name "unconnected-(U4B-Q-Pad5)") (class "Default")
      (node (ref "U4") (pin "5") (pinfunction "Q_5") (pintype "output"))
    )
    (net (code "149") (name "unconnected-(U4B-R{slash}C-Pad7)") (class "Default")
      (node (ref "U4") (pin "7") (pinfunction "R/C_7") (pintype "input"))
    )
    (net (code "150") (name "unconnected-(U4B-~{Q}-Pad12)") (class "Default")
      (node (ref "U4") (pin "12") (pinfunction "~{Q}_12") (pintype "output"))
    )
    (net (code "151") (name "~{BCSX}") (class "Default")
      (node (ref "P1") (pin "9") (pinfunction "~{CSX}_9") (pintype "bidirectional"))
      (node (ref "U1") (pin "2") (pinfunction "A_2") (pintype "bidirectional"))
    )
    (net (code "152") (name "~{BINH}") (class "Default")
      (node (ref "P1") (pin "17") (pinfunction "~{INH}_17") (pintype "bidirectional"))
      (node (ref "U2") (pin "12") (pinfunction "I0_12") (pintype "input"))
      (node (ref "U2") (pin "2") (pinfunction "I1_2") (pintype "input"))
      (node (ref "U2") (pin "9") (pinfunction "I0_9") (pintype "input"))
    )
    (net (code "153") (name "~{BIOSEL}") (class "Default")
      (node (ref "P1") (pin "18") (pinfunction "~{IOSEL}_18") (pintype "bidirectional"))
      (node (ref "U1") (pin "3") (pinfunction "A_3") (pintype "bidirectional"))
    )
    (net (code "154") (name "~{BRD}") (class "Default")
      (node (ref "P1") (pin "19") (pinfunction "~{RD}_19") (pintype "bidirectional"))
      (node (ref "U1") (pin "4") (pinfunction "A_4") (pintype "bidirectional"))
      (node (ref "U2") (pin "4") (pinfunction "I0_4") (pintype "input"))
    )
    (net (code "155") (name "~{BRST}") (class "Default")
      (node (ref "P1") (pin "10") (pinfunction "~{RST}_10") (pintype "bidirectional"))
      (node (ref "U3") (pin "9") (pinfunction "I_9") (pintype "input"))
    )
    (net (code "156") (name "~{BWAIT}") (class "Default")
      (node (ref "JP1") (pin "2") (pinfunction "2_2") (pintype "passive"))
      (node (ref "P1") (pin "16") (pinfunction "~{WAIT}_16") (pintype "bidirectional"))
    )
    (net (code "157") (name "~{BWR}") (class "Default")
      (node (ref "P1") (pin "20") (pinfunction "~{WR}_20") (pintype "bidirectional"))
      (node (ref "U1") (pin "5") (pinfunction "A_5") (pintype "bidirectional"))
      (node (ref "U2") (pin "5") (pinfunction "I1_5") (pintype "input"))
    )
    (net (code "158") (name "~{CSX}") (class "Default")
      (node (ref "U1") (pin "18") (pinfunction "B_18") (pintype "bidirectional"))
      (node (ref "U8") (pin "19") (pinfunction "~{OE}_19") (pintype "input"))
    )
    (net (code "159") (name "~{IOSEL}") (class "Default")
      (node (ref "U1") (pin "17") (pinfunction "B_17") (pintype "bidirectional"))
      (node (ref "U10") (pin "17") (pinfunction "P7_17") (pintype "input"))
      (node (ref "U11") (pin "40") (pinfunction "CE2_40") (pintype "input"))
      (node (ref "U2") (pin "10") (pinfunction "I1_10") (pintype "input"))
    )
    (net (code "160") (name "~{RD}") (class "Default")
      (node (ref "U1") (pin "16") (pinfunction "B_16") (pintype "bidirectional"))
      (node (ref "U11") (pin "41") (pinfunction "~{OE}_41") (pintype "input"))
      (node (ref "U6") (pin "22") (pinfunction "~{OE}_22") (pintype "input"))
      (node (ref "U8") (pin "1") (pinfunction "DIR_1") (pintype "input"))
      (node (ref "U9") (pin "1") (pinfunction "DIR_1") (pintype "input"))
    )
    (net (code "161") (name "~{ROM_CS}") (class "Default")
      (node (ref "JP2") (pin "2") (pinfunction "2_2") (pintype "passive"))
      (node (ref "R5") (pin "2") (pinfunction "2_2") (pintype "passive"))
      (node (ref "TP2") (pin "1") (pinfunction "1_1") (pintype "passive"))
      (node (ref "U2") (pin "1") (pinfunction "I0_1") (pintype "input"))
      (node (ref "U4") (pin "1") (pinfunction "A_1") (pintype "input"))
      (node (ref "U6") (pin "20") (pinfunction "~{CE}_20") (pintype "input"))
    )
    (net (code "162") (name "~{RST}") (class "Default")
      (node (ref "U3") (pin "10") (pinfunction "O_10") (pintype "output"))
      (node (ref "U4") (pin "3") (pinfunction "CLR_3") (pintype "input"))
    )
    (net (code "163") (name "~{WR}") (class "Default")
      (node (ref "U1") (pin "15") (pinfunction "B_15") (pintype "bidirectional"))
      (node (ref "U11") (pin "17") (pinfunction "~{WE}_17") (pintype "input"))
    )
  )
)
